# FPGA-5.net
KiCad netlist of a schematic drawn in Altium Designer
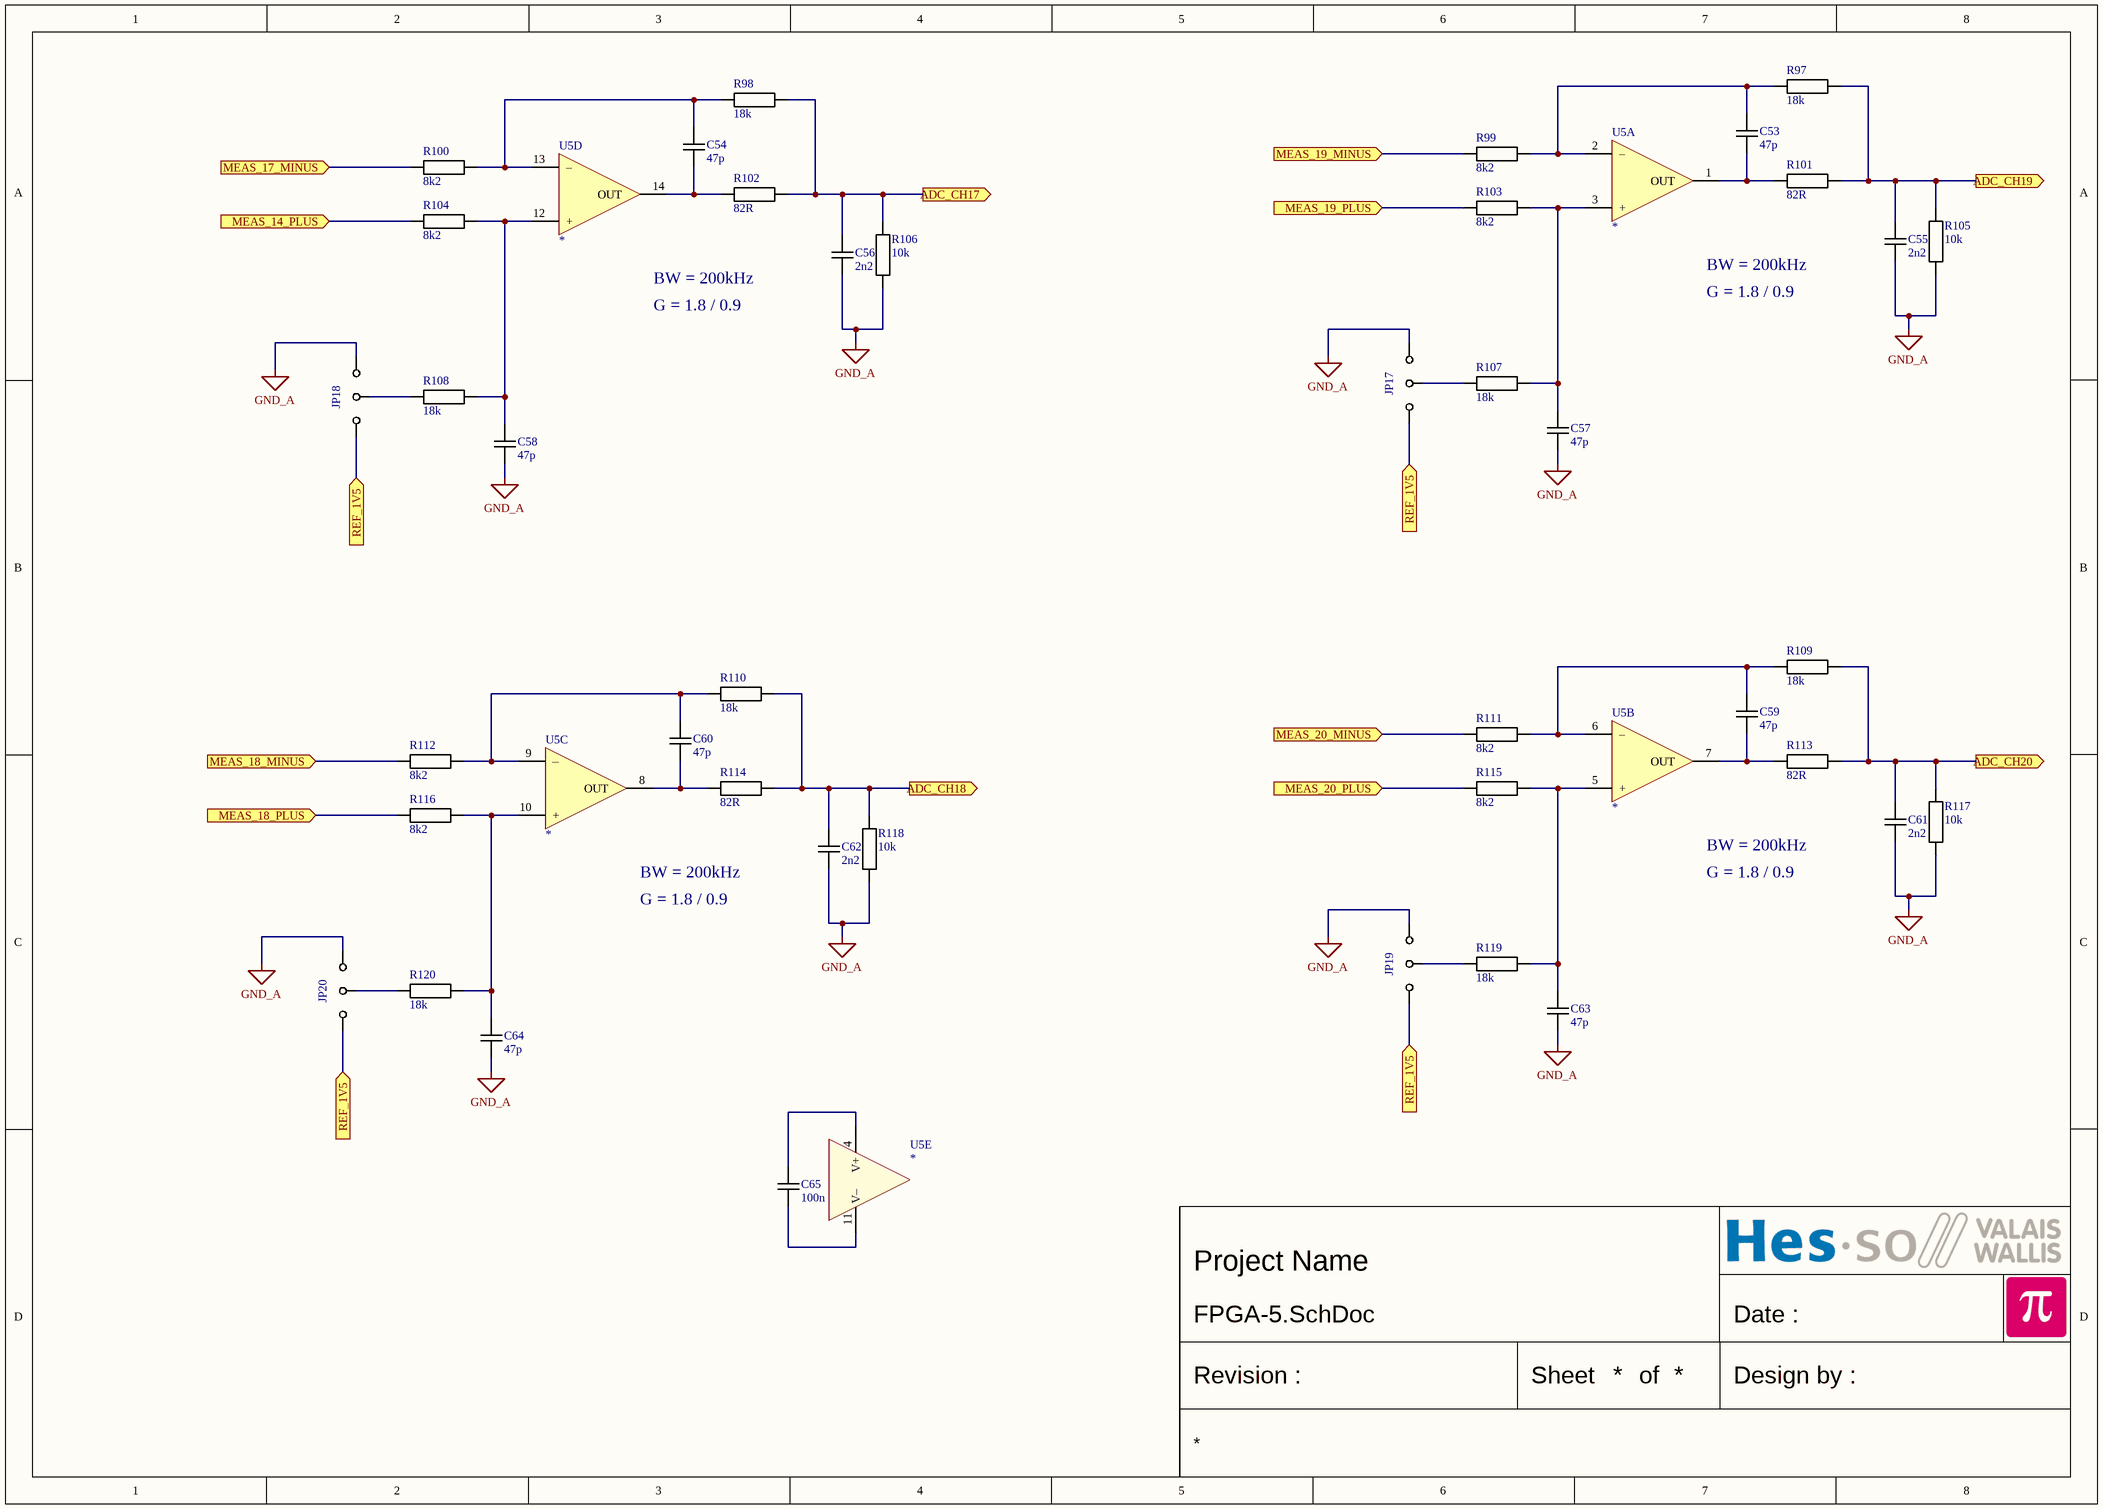
[diagram p0: FPGA-5.SchDoc]

(export (version "E")
  (design (tool "Eeschema 10.0.6"))
  (components
    (comp (ref "C53")
      (value "47p")
      (footprint "CAPACITOR 1608 REFLOW")
      (description "Capacitor X7R 10% 50V 1608(0603)")
      (libsource (lib "Capacitor") (part "Capacitor"))
    )
    (comp (ref "C54")
      (value "47p")
      (footprint "CAPACITOR 1608 REFLOW")
      (description "Capacitor X7R 10% 50V 1608(0603)")
      (libsource (lib "Capacitor") (part "Capacitor"))
    )
    (comp (ref "C55")
      (value "2n2")
      (footprint "CAPACITOR 1608 REFLOW")
      (description "Capacitor X7R 10% 50V 1608(0603)")
      (libsource (lib "Capacitor") (part "Capacitor"))
    )
    (comp (ref "C56")
      (value "2n2")
      (footprint "CAPACITOR 1608 REFLOW")
      (description "Capacitor X7R 10% 50V 1608(0603)")
      (libsource (lib "Capacitor") (part "Capacitor"))
    )
    (comp (ref "C57")
      (value "47p")
      (footprint "CAPACITOR 1608 REFLOW")
      (description "Capacitor X7R 10% 50V 1608(0603)")
      (libsource (lib "Capacitor") (part "Capacitor"))
    )
    (comp (ref "C58")
      (value "47p")
      (footprint "CAPACITOR 1608 REFLOW")
      (description "Capacitor X7R 10% 50V 1608(0603)")
      (libsource (lib "Capacitor") (part "Capacitor"))
    )
    (comp (ref "C59")
      (value "47p")
      (footprint "CAPACITOR 1608 REFLOW")
      (description "Capacitor X7R 10% 50V 1608(0603)")
      (libsource (lib "Capacitor") (part "Capacitor"))
    )
    (comp (ref "C60")
      (value "47p")
      (footprint "CAPACITOR 1608 REFLOW")
      (description "Capacitor X7R 10% 50V 1608(0603)")
      (libsource (lib "Capacitor") (part "Capacitor"))
    )
    (comp (ref "C61")
      (value "2n2")
      (footprint "CAPACITOR 1608 REFLOW")
      (description "Capacitor X7R 10% 50V 1608(0603)")
      (libsource (lib "Capacitor") (part "Capacitor"))
    )
    (comp (ref "C62")
      (value "2n2")
      (footprint "CAPACITOR 1608 REFLOW")
      (description "Capacitor X7R 10% 50V 1608(0603)")
      (libsource (lib "Capacitor") (part "Capacitor"))
    )
    (comp (ref "C63")
      (value "47p")
      (footprint "CAPACITOR 1608 REFLOW")
      (description "Capacitor X7R 10% 50V 1608(0603)")
      (libsource (lib "Capacitor") (part "Capacitor"))
    )
    (comp (ref "C64")
      (value "47p")
      (footprint "CAPACITOR 1608 REFLOW")
      (description "Capacitor X7R 10% 50V 1608(0603)")
      (libsource (lib "Capacitor") (part "Capacitor"))
    )
    (comp (ref "C65")
      (value "100n")
      (footprint "CAPACITOR 1608 REFLOW")
      (description "Capacitor X7R 10% 50V 1608(0603)")
      (libsource (lib "Capacitor") (part "Capacitor"))
    )
    (comp (ref "JP17")
      (value "{Value}")
      (footprint "JUMPER3 SMD 1608")
      (description "JUMPER 3 POS")
      (libsource (lib "Jumper") (part "JUMPER 3 POS"))
    )
    (comp (ref "JP18")
      (value "{Value}")
      (footprint "JUMPER3 SMD 1608")
      (description "JUMPER 3 POS")
      (libsource (lib "Jumper") (part "JUMPER 3 POS"))
    )
    (comp (ref "JP19")
      (value "{Value}")
      (footprint "JUMPER3 SMD 1608")
      (description "JUMPER 3 POS")
      (libsource (lib "Jumper") (part "JUMPER 3 POS"))
    )
    (comp (ref "JP20")
      (value "{Value}")
      (footprint "JUMPER3 SMD 1608")
      (description "JUMPER 3 POS")
      (libsource (lib "Jumper") (part "JUMPER 3 POS"))
    )
    (comp (ref "R97")
      (value "18k")
      (footprint "RESISTOR 1608 REFLOW")
      (description "Resistor 1% 50V 100mW 1608(0603)")
      (libsource (lib "Resistor") (part "Resistor"))
    )
    (comp (ref "R98")
      (value "18k")
      (footprint "RESISTOR 1608 REFLOW")
      (description "Resistor 1% 50V 100mW 1608(0603)")
      (libsource (lib "Resistor") (part "Resistor"))
    )
    (comp (ref "R99")
      (value "8k2")
      (footprint "RESISTOR 1608 REFLOW")
      (description "Resistor 1% 50V 100mW 1608(0603)")
      (libsource (lib "Resistor") (part "Resistor"))
    )
    (comp (ref "R100")
      (value "8k2")
      (footprint "RESISTOR 1608 REFLOW")
      (description "Resistor 1% 50V 100mW 1608(0603)")
      (libsource (lib "Resistor") (part "Resistor"))
    )
    (comp (ref "R101")
      (value "82R")
      (footprint "RESISTOR 1608 REFLOW")
      (description "Resistor 1% 50V 100mW 1608(0603)")
      (libsource (lib "Resistor") (part "Resistor"))
    )
    (comp (ref "R102")
      (value "82R")
      (footprint "RESISTOR 1608 REFLOW")
      (description "Resistor 1% 50V 100mW 1608(0603)")
      (libsource (lib "Resistor") (part "Resistor"))
    )
    (comp (ref "R103")
      (value "8k2")
      (footprint "RESISTOR 1608 REFLOW")
      (description "Resistor 1% 50V 100mW 1608(0603)")
      (libsource (lib "Resistor") (part "Resistor"))
    )
    (comp (ref "R104")
      (value "8k2")
      (footprint "RESISTOR 1608 REFLOW")
      (description "Resistor 1% 50V 100mW 1608(0603)")
      (libsource (lib "Resistor") (part "Resistor"))
    )
    (comp (ref "R105")
      (value "10k")
      (footprint "RESISTOR 1608 REFLOW")
      (description "Resistor 1% 50V 100mW 1608(0603)")
      (libsource (lib "Resistor") (part "Resistor"))
    )
    (comp (ref "R106")
      (value "10k")
      (footprint "RESISTOR 1608 REFLOW")
      (description "Resistor 1% 50V 100mW 1608(0603)")
      (libsource (lib "Resistor") (part "Resistor"))
    )
    (comp (ref "R107")
      (value "18k")
      (footprint "RESISTOR 1608 REFLOW")
      (description "Resistor 1% 50V 100mW 1608(0603)")
      (libsource (lib "Resistor") (part "Resistor"))
    )
    (comp (ref "R108")
      (value "18k")
      (footprint "RESISTOR 1608 REFLOW")
      (description "Resistor 1% 50V 100mW 1608(0603)")
      (libsource (lib "Resistor") (part "Resistor"))
    )
    (comp (ref "R109")
      (value "18k")
      (footprint "RESISTOR 1608 REFLOW")
      (description "Resistor 1% 50V 100mW 1608(0603)")
      (libsource (lib "Resistor") (part "Resistor"))
    )
    (comp (ref "R110")
      (value "18k")
      (footprint "RESISTOR 1608 REFLOW")
      (description "Resistor 1% 50V 100mW 1608(0603)")
      (libsource (lib "Resistor") (part "Resistor"))
    )
    (comp (ref "R111")
      (value "8k2")
      (footprint "RESISTOR 1608 REFLOW")
      (description "Resistor 1% 50V 100mW 1608(0603)")
      (libsource (lib "Resistor") (part "Resistor"))
    )
    (comp (ref "R112")
      (value "8k2")
      (footprint "RESISTOR 1608 REFLOW")
      (description "Resistor 1% 50V 100mW 1608(0603)")
      (libsource (lib "Resistor") (part "Resistor"))
    )
    (comp (ref "R113")
      (value "82R")
      (footprint "RESISTOR 1608 REFLOW")
      (description "Resistor 1% 50V 100mW 1608(0603)")
      (libsource (lib "Resistor") (part "Resistor"))
    )
    (comp (ref "R114")
      (value "82R")
      (footprint "RESISTOR 1608 REFLOW")
      (description "Resistor 1% 50V 100mW 1608(0603)")
      (libsource (lib "Resistor") (part "Resistor"))
    )
    (comp (ref "R115")
      (value "8k2")
      (footprint "RESISTOR 1608 REFLOW")
      (description "Resistor 1% 50V 100mW 1608(0603)")
      (libsource (lib "Resistor") (part "Resistor"))
    )
    (comp (ref "R116")
      (value "8k2")
      (footprint "RESISTOR 1608 REFLOW")
      (description "Resistor 1% 50V 100mW 1608(0603)")
      (libsource (lib "Resistor") (part "Resistor"))
    )
    (comp (ref "R117")
      (value "10k")
      (footprint "RESISTOR 1608 REFLOW")
      (description "Resistor 1% 50V 100mW 1608(0603)")
      (libsource (lib "Resistor") (part "Resistor"))
    )
    (comp (ref "R118")
      (value "10k")
      (footprint "RESISTOR 1608 REFLOW")
      (description "Resistor 1% 50V 100mW 1608(0603)")
      (libsource (lib "Resistor") (part "Resistor"))
    )
    (comp (ref "R119")
      (value "18k")
      (footprint "RESISTOR 1608 REFLOW")
      (description "Resistor 1% 50V 100mW 1608(0603)")
      (libsource (lib "Resistor") (part "Resistor"))
    )
    (comp (ref "R120")
      (value "18k")
      (footprint "RESISTOR 1608 REFLOW")
      (description "Resistor 1% 50V 100mW 1608(0603)")
      (libsource (lib "Resistor") (part "Resistor"))
    )
    (comp (ref "U5")
      (value "*")
      (footprint "SO14 P1.27 C4.0X8.8 H1.75")
      (description "Generic quad OPA 14 pins")
      (libsource (lib "Amplifier") (part "OPA QUAD"))
    )
  )
  (nets
    (net (code "1") (name "/ADC_CH17") (class "Default")
      (node (ref "C56") (pin "2") (pinfunction "2_2") (pintype "passive"))
      (node (ref "R102") (pin "2") (pinfunction "2_2") (pintype "passive"))
      (node (ref "R106") (pin "1") (pinfunction "1_1") (pintype "passive"))
      (node (ref "R98") (pin "2") (pinfunction "2_2") (pintype "passive"))
    )
    (net (code "2") (name "/ADC_CH18") (class "Default")
      (node (ref "C62") (pin "2") (pinfunction "2_2") (pintype "passive"))
      (node (ref "R110") (pin "2") (pinfunction "2_2") (pintype "passive"))
      (node (ref "R114") (pin "2") (pinfunction "2_2") (pintype "passive"))
      (node (ref "R118") (pin "1") (pinfunction "1_1") (pintype "passive"))
    )
    (net (code "3") (name "/ADC_CH19") (class "Default")
      (node (ref "C55") (pin "2") (pinfunction "2_2") (pintype "passive"))
      (node (ref "R101") (pin "2") (pinfunction "2_2") (pintype "passive"))
      (node (ref "R105") (pin "1") (pinfunction "1_1") (pintype "passive"))
      (node (ref "R97") (pin "2") (pinfunction "2_2") (pintype "passive"))
    )
    (net (code "4") (name "/ADC_CH20") (class "Default")
      (node (ref "C61") (pin "2") (pinfunction "2_2") (pintype "passive"))
      (node (ref "R109") (pin "2") (pinfunction "2_2") (pintype "passive"))
      (node (ref "R113") (pin "2") (pinfunction "2_2") (pintype "passive"))
      (node (ref "R117") (pin "1") (pinfunction "1_1") (pintype "passive"))
    )
    (net (code "5") (name "/MEAS_14_PLUS") (class "Default")
      (node (ref "R104") (pin "1") (pinfunction "1_1") (pintype "passive"))
    )
    (net (code "6") (name "/MEAS_17_MINUS") (class "Default")
      (node (ref "R100") (pin "1") (pinfunction "1_1") (pintype "passive"))
    )
    (net (code "7") (name "/MEAS_18_MINUS") (class "Default")
      (node (ref "R112") (pin "1") (pinfunction "1_1") (pintype "passive"))
    )
    (net (code "8") (name "/MEAS_18_PLUS") (class "Default")
      (node (ref "R116") (pin "1") (pinfunction "1_1") (pintype "passive"))
    )
    (net (code "9") (name "/MEAS_19_MINUS") (class "Default")
      (node (ref "R99") (pin "1") (pinfunction "1_1") (pintype "passive"))
    )
    (net (code "10") (name "/MEAS_19_PLUS") (class "Default")
      (node (ref "R103") (pin "1") (pinfunction "1_1") (pintype "passive"))
    )
    (net (code "11") (name "/MEAS_20_MINUS") (class "Default")
      (node (ref "R111") (pin "1") (pinfunction "1_1") (pintype "passive"))
    )
    (net (code "12") (name "/MEAS_20_PLUS") (class "Default")
      (node (ref "R115") (pin "1") (pinfunction "1_1") (pintype "passive"))
    )
    (net (code "13") (name "/REF_1V5") (class "Default")
      (node (ref "JP17") (pin "1") (pinfunction "1_1") (pintype "passive"))
      (node (ref "JP18") (pin "1") (pinfunction "1_1") (pintype "passive"))
      (node (ref "JP19") (pin "1") (pinfunction "1_1") (pintype "passive"))
      (node (ref "JP20") (pin "1") (pinfunction "1_1") (pintype "passive"))
    )
    (net (code "14") (name "GND_A") (class "Default")
      (node (ref "C55") (pin "1") (pinfunction "1_1") (pintype "passive"))
      (node (ref "C56") (pin "1") (pinfunction "1_1") (pintype "passive"))
      (node (ref "C57") (pin "1") (pinfunction "1_1") (pintype "passive"))
      (node (ref "C58") (pin "1") (pinfunction "1_1") (pintype "passive"))
      (node (ref "C61") (pin "1") (pinfunction "1_1") (pintype "passive"))
      (node (ref "C62") (pin "1") (pinfunction "1_1") (pintype "passive"))
      (node (ref "C63") (pin "1") (pinfunction "1_1") (pintype "passive"))
      (node (ref "C64") (pin "1") (pinfunction "1_1") (pintype "passive"))
      (node (ref "JP17") (pin "3") (pinfunction "3_3") (pintype "passive"))
      (node (ref "JP18") (pin "3") (pinfunction "3_3") (pintype "passive"))
      (node (ref "JP19") (pin "3") (pinfunction "3_3") (pintype "passive"))
      (node (ref "JP20") (pin "3") (pinfunction "3_3") (pintype "passive"))
      (node (ref "R105") (pin "2") (pinfunction "2_2") (pintype "passive"))
      (node (ref "R106") (pin "2") (pinfunction "2_2") (pintype "passive"))
      (node (ref "R117") (pin "2") (pinfunction "2_2") (pintype "passive"))
      (node (ref "R118") (pin "2") (pinfunction "2_2") (pintype "passive"))
    )
    (net (code "15") (name "Net-(JP17-Pad2)") (class "Default")
      (node (ref "JP17") (pin "2") (pinfunction "2_2") (pintype "passive"))
      (node (ref "R107") (pin "2") (pinfunction "2_2") (pintype "passive"))
    )
    (net (code "16") (name "Net-(JP18-Pad2)") (class "Default")
      (node (ref "JP18") (pin "2") (pinfunction "2_2") (pintype "passive"))
      (node (ref "R108") (pin "2") (pinfunction "2_2") (pintype "passive"))
    )
    (net (code "17") (name "Net-(JP19-Pad2)") (class "Default")
      (node (ref "JP19") (pin "2") (pinfunction "2_2") (pintype "passive"))
      (node (ref "R119") (pin "2") (pinfunction "2_2") (pintype "passive"))
    )
    (net (code "18") (name "Net-(JP20-Pad2)") (class "Default")
      (node (ref "JP20") (pin "2") (pinfunction "2_2") (pintype "passive"))
      (node (ref "R120") (pin "2") (pinfunction "2_2") (pintype "passive"))
    )
    (net (code "19") (name "Net-(U5A-+)") (class "Default")
      (node (ref "C57") (pin "2") (pinfunction "2_2") (pintype "passive"))
      (node (ref "R103") (pin "2") (pinfunction "2_2") (pintype "passive"))
      (node (ref "R107") (pin "1") (pinfunction "1_1") (pintype "passive"))
      (node (ref "U5") (pin "3") (pinfunction "+_3") (pintype "passive"))
    )
    (net (code "20") (name "Net-(U5A-OUT)") (class "Default")
      (node (ref "C53") (pin "1") (pinfunction "1_1") (pintype "passive"))
      (node (ref "R101") (pin "1") (pinfunction "1_1") (pintype "passive"))
      (node (ref "U5") (pin "1") (pinfunction "OUT_1") (pintype "passive"))
    )
    (net (code "21") (name "Net-(U5A-–)") (class "Default")
      (node (ref "C53") (pin "2") (pinfunction "2_2") (pintype "passive"))
      (node (ref "R97") (pin "1") (pinfunction "1_1") (pintype "passive"))
      (node (ref "R99") (pin "2") (pinfunction "2_2") (pintype "passive"))
      (node (ref "U5") (pin "2") (pinfunction "–_2") (pintype "passive"))
    )
    (net (code "22") (name "Net-(U5B-+)") (class "Default")
      (node (ref "C63") (pin "2") (pinfunction "2_2") (pintype "passive"))
      (node (ref "R115") (pin "2") (pinfunction "2_2") (pintype "passive"))
      (node (ref "R119") (pin "1") (pinfunction "1_1") (pintype "passive"))
      (node (ref "U5") (pin "5") (pinfunction "+_5") (pintype "passive"))
    )
    (net (code "23") (name "Net-(U5B-OUT)") (class "Default")
      (node (ref "C59") (pin "1") (pinfunction "1_1") (pintype "passive"))
      (node (ref "R113") (pin "1") (pinfunction "1_1") (pintype "passive"))
      (node (ref "U5") (pin "7") (pinfunction "OUT_7") (pintype "passive"))
    )
    (net (code "24") (name "Net-(U5B-–)") (class "Default")
      (node (ref "C59") (pin "2") (pinfunction "2_2") (pintype "passive"))
      (node (ref "R109") (pin "1") (pinfunction "1_1") (pintype "passive"))
      (node (ref "R111") (pin "2") (pinfunction "2_2") (pintype "passive"))
      (node (ref "U5") (pin "6") (pinfunction "–_6") (pintype "passive"))
    )
    (net (code "25") (name "Net-(U5C-+)") (class "Default")
      (node (ref "C64") (pin "2") (pinfunction "2_2") (pintype "passive"))
      (node (ref "R116") (pin "2") (pinfunction "2_2") (pintype "passive"))
      (node (ref "R120") (pin "1") (pinfunction "1_1") (pintype "passive"))
      (node (ref "U5") (pin "10") (pinfunction "+_10") (pintype "passive"))
    )
    (net (code "26") (name "Net-(U5C-OUT)") (class "Default")
      (node (ref "C60") (pin "1") (pinfunction "1_1") (pintype "passive"))
      (node (ref "R114") (pin "1") (pinfunction "1_1") (pintype "passive"))
      (node (ref "U5") (pin "8") (pinfunction "OUT_8") (pintype "passive"))
    )
    (net (code "27") (name "Net-(U5C-–)") (class "Default")
      (node (ref "C60") (pin "2") (pinfunction "2_2") (pintype "passive"))
      (node (ref "R110") (pin "1") (pinfunction "1_1") (pintype "passive"))
      (node (ref "R112") (pin "2") (pinfunction "2_2") (pintype "passive"))
      (node (ref "U5") (pin "9") (pinfunction "–_9") (pintype "passive"))
    )
    (net (code "28") (name "Net-(U5D-+)") (class "Default")
      (node (ref "C58") (pin "2") (pinfunction "2_2") (pintype "passive"))
      (node (ref "R104") (pin "2") (pinfunction "2_2") (pintype "passive"))
      (node (ref "R108") (pin "1") (pinfunction "1_1") (pintype "passive"))
      (node (ref "U5") (pin "12") (pinfunction "+_12") (pintype "passive"))
    )
    (net (code "29") (name "Net-(U5D-OUT)") (class "Default")
      (node (ref "C54") (pin "1") (pinfunction "1_1") (pintype "passive"))
      (node (ref "R102") (pin "1") (pinfunction "1_1") (pintype "passive"))
      (node (ref "U5") (pin "14") (pinfunction "OUT_14") (pintype "passive"))
    )
    (net (code "30") (name "Net-(U5D-–)") (class "Default")
      (node (ref "C54") (pin "2") (pinfunction "2_2") (pintype "passive"))
      (node (ref "R100") (pin "2") (pinfunction "2_2") (pintype "passive"))
      (node (ref "R98") (pin "1") (pinfunction "1_1") (pintype "passive"))
      (node (ref "U5") (pin "13") (pinfunction "–_13") (pintype "passive"))
    )
    (net (code "31") (name "Net-(U5E-V+)") (class "Default")
      (node (ref "C65") (pin "2") (pinfunction "2_2") (pintype "passive"))
      (node (ref "U5") (pin "4") (pinfunction "V+_4") (pintype "passive"))
    )
    (net (code "32") (name "Net-(U5E-V–)") (class "Default")
      (node (ref "C65") (pin "1") (pinfunction "1_1") (pintype "passive"))
      (node (ref "U5") (pin "11") (pinfunction "V–_11") (pintype "passive"))
    )
  )
)
